# dof_evm.net
KiCad netlist of a schematic drawn in Altium Designer
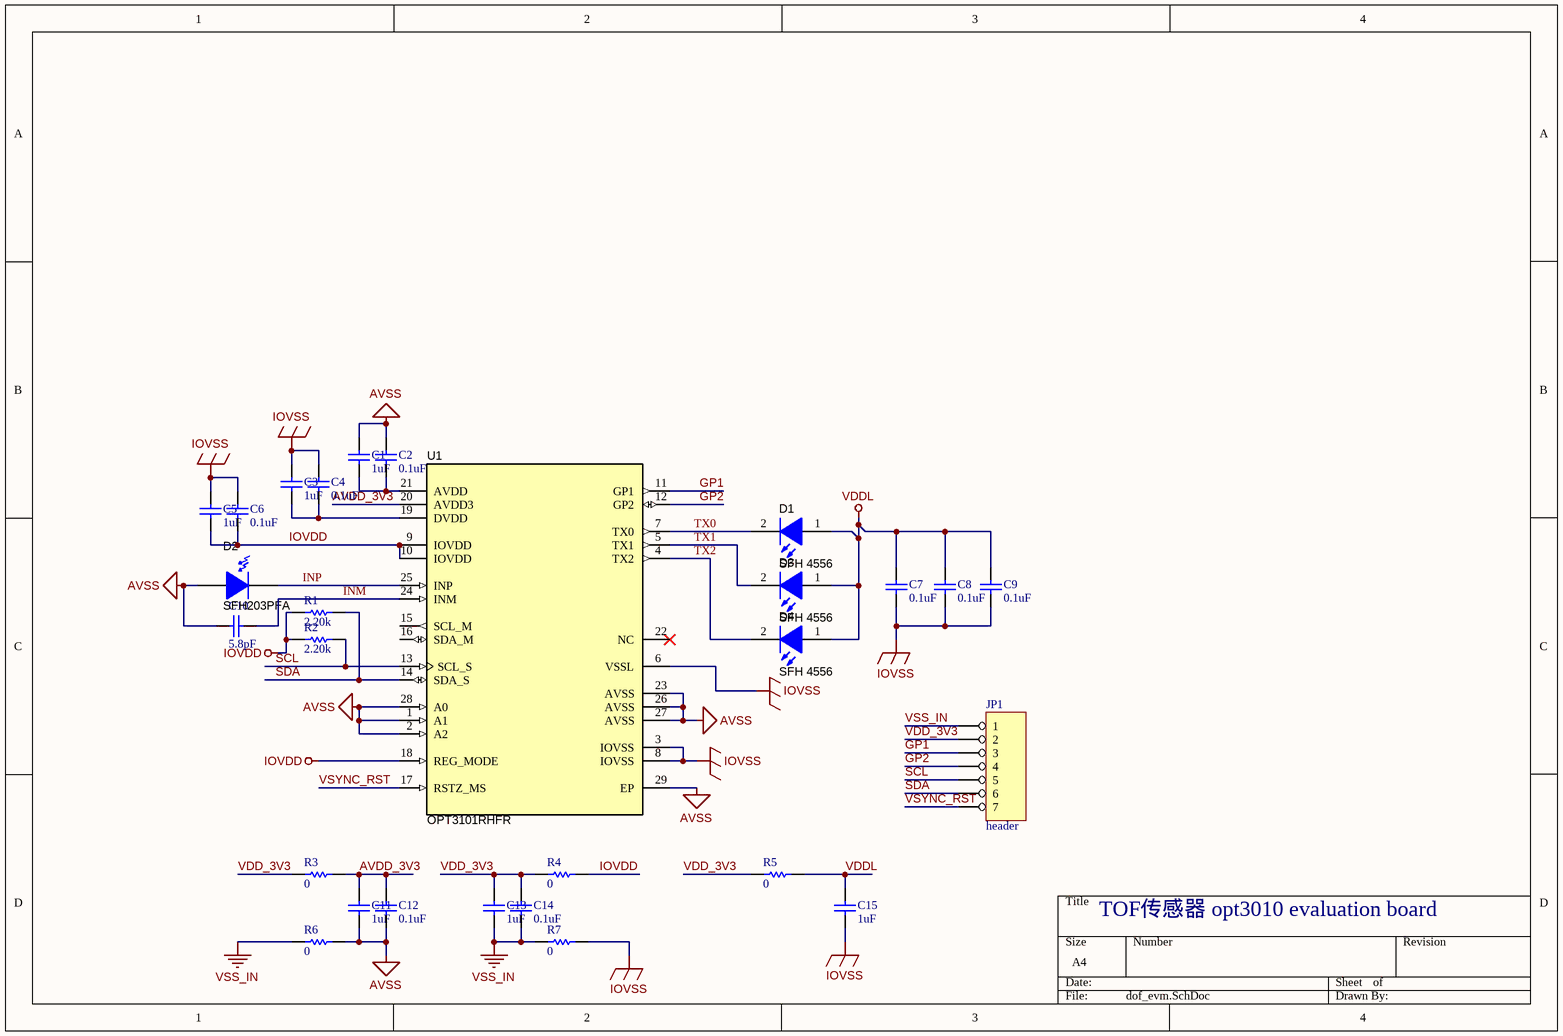
[diagram p0: dof_evm.SchDoc]

(export (version "E")
  (design (tool "Eeschema 10.0.6"))
  (components
    (comp (ref "C1")
      (value "1uF")
      (footprint "0603_C")
      (description "Capacitor")
      (fields (field (name "PUBLISHER") "Altium Limited"))
      (libsource (lib "My Footprint") (part "CAP"))
    )
    (comp (ref "C2")
      (value "0.1uF")
      (footprint "0603_C")
      (description "Capacitor")
      (fields (field (name "PUBLISHER") "Altium Limited"))
      (libsource (lib "My Footprint") (part "CAP"))
    )
    (comp (ref "C3")
      (value "1uF")
      (footprint "0603_C")
      (description "Capacitor")
      (fields (field (name "PUBLISHER") "Altium Limited"))
      (libsource (lib "My Footprint") (part "CAP"))
    )
    (comp (ref "C4")
      (value "0.1uF")
      (footprint "0603_C")
      (description "Capacitor")
      (fields (field (name "PUBLISHER") "Altium Limited"))
      (libsource (lib "My Footprint") (part "CAP"))
    )
    (comp (ref "C5")
      (value "1uF")
      (footprint "0603_C")
      (description "Capacitor")
      (fields (field (name "PUBLISHER") "Altium Limited"))
      (libsource (lib "My Footprint") (part "CAP"))
    )
    (comp (ref "C6")
      (value "0.1uF")
      (footprint "0603_C")
      (description "Capacitor")
      (fields (field (name "PUBLISHER") "Altium Limited"))
      (libsource (lib "My Footprint") (part "CAP"))
    )
    (comp (ref "C7")
      (value "0.1uF")
      (footprint "0603_C")
      (description "Capacitor")
      (fields (field (name "PUBLISHER") "Altium Limited"))
      (libsource (lib "My Footprint") (part "CAP"))
    )
    (comp (ref "C8")
      (value "0.1uF")
      (footprint "0603_C")
      (description "Capacitor")
      (fields (field (name "PUBLISHER") "Altium Limited"))
      (libsource (lib "My Footprint") (part "CAP"))
    )
    (comp (ref "C9")
      (value "0.1uF")
      (footprint "0603_C")
      (description "Capacitor")
      (fields (field (name "PUBLISHER") "Altium Limited"))
      (libsource (lib "My Footprint") (part "CAP"))
    )
    (comp (ref "C10")
      (value "5.8pF")
      (footprint "0603_C")
      (description "Capacitor")
      (fields (field (name "PUBLISHER") "Altium Limited"))
      (libsource (lib "My Footprint") (part "CAP"))
    )
    (comp (ref "C11")
      (value "1uF")
      (footprint "0603_C")
      (description "Capacitor")
      (fields (field (name "PUBLISHER") "Altium Limited"))
      (libsource (lib "My Footprint") (part "CAP"))
    )
    (comp (ref "C12")
      (value "0.1uF")
      (footprint "0603_C")
      (description "Capacitor")
      (fields (field (name "PUBLISHER") "Altium Limited"))
      (libsource (lib "My Footprint") (part "CAP"))
    )
    (comp (ref "C13")
      (value "1uF")
      (footprint "0603_C")
      (description "Capacitor")
      (fields (field (name "PUBLISHER") "Altium Limited"))
      (libsource (lib "My Footprint") (part "CAP"))
    )
    (comp (ref "C14")
      (value "0.1uF")
      (footprint "0603_C")
      (description "Capacitor")
      (fields (field (name "PUBLISHER") "Altium Limited"))
      (libsource (lib "My Footprint") (part "CAP"))
    )
    (comp (ref "C15")
      (value "1uF")
      (footprint "0603_C")
      (description "Capacitor")
      (fields (field (name "PUBLISHER") "Altium Limited"))
      (libsource (lib "My Footprint") (part "CAP"))
    )
    (comp (ref "D1")
      (value "SFH 4556")
      (footprint "SFH4556")
      (description "LED, Infrared, TH")
      (fields (field (name "MANUFACTURER") "OSRAM") (field (name "PUBLISHER") "Texas Instruments"))
      (libsource (lib "My Footprint") (part "SFH 4556"))
    )
    (comp (ref "D2")
      (value "SFH203PFA")
      (footprint "SFH_213")
      (description "Silicon PIN Photodiode, TH")
      (fields (field (name "MANUFACTURER") "OSRAM"))
      (libsource (lib "My Footprint") (part "SFH203PFA"))
    )
    (comp (ref "D3")
      (value "SFH 4556")
      (footprint "SFH4556")
      (description "LED, Infrared, TH")
      (fields (field (name "MANUFACTURER") "OSRAM") (field (name "PUBLISHER") "Texas Instruments"))
      (libsource (lib "My Footprint") (part "SFH 4556"))
    )
    (comp (ref "D4")
      (value "SFH 4556")
      (footprint "SFH4556")
      (description "LED, Infrared, TH")
      (fields (field (name "MANUFACTURER") "OSRAM") (field (name "PUBLISHER") "Texas Instruments"))
      (libsource (lib "My Footprint") (part "SFH 4556"))
    )
    (comp (ref "JP1")
      (value "header")
      (footprint "header7")
      (libsource (lib "My Footprint") (part "HEADER 7"))
    )
    (comp (ref "R1")
      (value "2.20k")
      (footprint "0603_R")
      (description "Resistor")
      (fields (field (name "PUBLISHER") "Altium Limited"))
      (libsource (lib "My Footprint") (part "RES"))
    )
    (comp (ref "R2")
      (value "2.20k")
      (footprint "0603_R")
      (description "Resistor")
      (fields (field (name "PUBLISHER") "Altium Limited"))
      (libsource (lib "My Footprint") (part "RES"))
    )
    (comp (ref "R3")
      (value "0")
      (footprint "0603_R")
      (description "Resistor")
      (fields (field (name "PUBLISHER") "Altium Limited"))
      (libsource (lib "My Footprint") (part "RES"))
    )
    (comp (ref "R4")
      (value "0")
      (footprint "0603_R")
      (description "Resistor")
      (fields (field (name "PUBLISHER") "Altium Limited"))
      (libsource (lib "My Footprint") (part "RES"))
    )
    (comp (ref "R5")
      (value "0")
      (footprint "0603_R")
      (description "Resistor")
      (fields (field (name "PUBLISHER") "Altium Limited"))
      (libsource (lib "My Footprint") (part "RES"))
    )
    (comp (ref "R6")
      (value "0")
      (footprint "0603_R")
      (description "Resistor")
      (fields (field (name "PUBLISHER") "Altium Limited"))
      (libsource (lib "My Footprint") (part "RES"))
    )
    (comp (ref "R7")
      (value "0")
      (footprint "0603_R")
      (description "Resistor")
      (fields (field (name "PUBLISHER") "Altium Limited"))
      (libsource (lib "My Footprint") (part "RES"))
    )
    (comp (ref "U1")
      (value "OPT3101RHFR")
      (footprint "VQFN-28")
      (description "Long Range Proximity/Depth Sensor, RHF0028A (VQFN-28)")
      (fields
        (field (name "ALTERNATE PARTNUMBER") "OPT3101RHFT")
        (field (name "MANUFACTURER") "Texas Instruments")
        (field (name "PUBLISHER") "Texas Instruments")
      )
      (libsource (lib "My Footprint") (part "OPT3101RHFR"))
    )
  )
  (nets
    (net (code "1") (name "/AVDD_3V3") (class "Default")
      (node (ref "C11") (pin "2") (pinfunction "2_2") (pintype "passive"))
      (node (ref "C12") (pin "2") (pinfunction "2_2") (pintype "passive"))
      (node (ref "R3") (pin "2") (pinfunction "2_2") (pintype "passive"))
      (node (ref "U1") (pin "20") (pinfunction "AVDD3_20") (pintype "power_in"))
    )
    (net (code "2") (name "/GP1") (class "Default")
      (node (ref "JP1") (pin "3") (pinfunction "3_3") (pintype "passive"))
      (node (ref "U1") (pin "11") (pinfunction "GP1_11") (pintype "output"))
    )
    (net (code "3") (name "/GP2") (class "Default")
      (node (ref "JP1") (pin "4") (pinfunction "4_4") (pintype "passive"))
      (node (ref "U1") (pin "12") (pinfunction "GP2_12") (pintype "bidirectional"))
    )
    (net (code "4") (name "/INM") (class "Default")
      (node (ref "C10") (pin "1") (pinfunction "1_1") (pintype "passive"))
      (node (ref "U1") (pin "24") (pinfunction "INM_24") (pintype "input"))
    )
    (net (code "5") (name "/INP") (class "Default")
      (node (ref "D2") (pin "2") (pinfunction "C_2") (pintype "passive"))
      (node (ref "U1") (pin "25") (pinfunction "INP_25") (pintype "input"))
    )
    (net (code "6") (name "/SCL") (class "Default")
      (node (ref "JP1") (pin "5") (pinfunction "5_5") (pintype "passive"))
      (node (ref "R2") (pin "2") (pinfunction "2_2") (pintype "passive"))
      (node (ref "U1") (pin "13") (pinfunction "SCL_S_13") (pintype "input"))
    )
    (net (code "7") (name "/SDA") (class "Default")
      (node (ref "JP1") (pin "6") (pinfunction "6_6") (pintype "passive"))
      (node (ref "R1") (pin "2") (pinfunction "2_2") (pintype "passive"))
      (node (ref "U1") (pin "14") (pinfunction "SDA_S_14") (pintype "bidirectional"))
    )
    (net (code "8") (name "/TX0") (class "Default")
      (node (ref "D1") (pin "2") (pinfunction "K_2") (pintype "passive"))
      (node (ref "U1") (pin "7") (pinfunction "TX0_7") (pintype "output"))
    )
    (net (code "9") (name "/TX1") (class "Default")
      (node (ref "D3") (pin "2") (pinfunction "K_2") (pintype "passive"))
      (node (ref "U1") (pin "5") (pinfunction "TX1_5") (pintype "output"))
    )
    (net (code "10") (name "/TX2") (class "Default")
      (node (ref "D4") (pin "2") (pinfunction "K_2") (pintype "passive"))
      (node (ref "U1") (pin "4") (pinfunction "TX2_4") (pintype "output"))
    )
    (net (code "11") (name "/VDD_3V3") (class "Default")
      (node (ref "C13") (pin "2") (pinfunction "2_2") (pintype "passive"))
      (node (ref "C14") (pin "2") (pinfunction "2_2") (pintype "passive"))
      (node (ref "JP1") (pin "2") (pinfunction "2_2") (pintype "passive"))
      (node (ref "R3") (pin "1") (pinfunction "1_1") (pintype "passive"))
      (node (ref "R4") (pin "1") (pinfunction "1_1") (pintype "passive"))
      (node (ref "R5") (pin "1") (pinfunction "1_1") (pintype "passive"))
    )
    (net (code "12") (name "/VSYNC_RST") (class "Default")
      (node (ref "JP1") (pin "7") (pinfunction "7_7") (pintype "passive"))
      (node (ref "U1") (pin "17") (pinfunction "RSTZ_MS_17") (pintype "input"))
    )
    (net (code "13") (name "AVSS") (class "Default")
      (node (ref "C1") (pin "2") (pinfunction "2_2") (pintype "passive"))
      (node (ref "C10") (pin "2") (pinfunction "2_2") (pintype "passive"))
      (node (ref "C11") (pin "1") (pinfunction "1_1") (pintype "passive"))
      (node (ref "C12") (pin "1") (pinfunction "1_1") (pintype "passive"))
      (node (ref "C2") (pin "2") (pinfunction "2_2") (pintype "passive"))
      (node (ref "D2") (pin "1") (pinfunction "A_1") (pintype "passive"))
      (node (ref "R6") (pin "2") (pinfunction "2_2") (pintype "passive"))
      (node (ref "U1") (pin "1") (pinfunction "A1_1") (pintype "input"))
      (node (ref "U1") (pin "2") (pinfunction "A2_2") (pintype "input"))
      (node (ref "U1") (pin "23") (pinfunction "AVSS_23") (pintype "power_in"))
      (node (ref "U1") (pin "26") (pinfunction "AVSS_26") (pintype "power_in"))
      (node (ref "U1") (pin "27") (pinfunction "AVSS_27") (pintype "power_in"))
      (node (ref "U1") (pin "28") (pinfunction "A0_28") (pintype "input"))
      (node (ref "U1") (pin "29") (pinfunction "EP_29") (pintype "passive"))
    )
    (net (code "14") (name "IOVDD") (class "Default")
      (node (ref "C5") (pin "1") (pinfunction "1_1") (pintype "passive"))
      (node (ref "C6") (pin "1") (pinfunction "1_1") (pintype "passive"))
      (node (ref "R1") (pin "1") (pinfunction "1_1") (pintype "passive"))
      (node (ref "R2") (pin "1") (pinfunction "1_1") (pintype "passive"))
      (node (ref "R4") (pin "2") (pinfunction "2_2") (pintype "passive"))
      (node (ref "U1") (pin "10") (pinfunction "IOVDD_10") (pintype "power_in"))
      (node (ref "U1") (pin "18") (pinfunction "REG_MODE_18") (pintype "input"))
      (node (ref "U1") (pin "9") (pinfunction "IOVDD_9") (pintype "power_in"))
    )
    (net (code "15") (name "IOVSS") (class "Default")
      (node (ref "C15") (pin "1") (pinfunction "1_1") (pintype "passive"))
      (node (ref "C3") (pin "2") (pinfunction "2_2") (pintype "passive"))
      (node (ref "C4") (pin "2") (pinfunction "2_2") (pintype "passive"))
      (node (ref "C5") (pin "2") (pinfunction "2_2") (pintype "passive"))
      (node (ref "C6") (pin "2") (pinfunction "2_2") (pintype "passive"))
      (node (ref "C7") (pin "1") (pinfunction "1_1") (pintype "passive"))
      (node (ref "C8") (pin "1") (pinfunction "1_1") (pintype "passive"))
      (node (ref "C9") (pin "1") (pinfunction "1_1") (pintype "passive"))
      (node (ref "R7") (pin "2") (pinfunction "2_2") (pintype "passive"))
      (node (ref "U1") (pin "3") (pinfunction "IOVSS_3") (pintype "power_in"))
      (node (ref "U1") (pin "6") (pinfunction "VSSL_6") (pintype "power_in"))
      (node (ref "U1") (pin "8") (pinfunction "IOVSS_8") (pintype "power_in"))
    )
    (net (code "16") (name "Net-(U1-AVDD)") (class "Default")
      (node (ref "C1") (pin "1") (pinfunction "1_1") (pintype "passive"))
      (node (ref "C2") (pin "1") (pinfunction "1_1") (pintype "passive"))
      (node (ref "U1") (pin "21") (pinfunction "AVDD_21") (pintype "power_in"))
    )
    (net (code "17") (name "Net-(U1-DVDD)") (class "Default")
      (node (ref "C3") (pin "1") (pinfunction "1_1") (pintype "passive"))
      (node (ref "C4") (pin "1") (pinfunction "1_1") (pintype "passive"))
      (node (ref "U1") (pin "19") (pinfunction "DVDD_19") (pintype "power_in"))
    )
    (net (code "18") (name "VDDL") (class "Default")
      (node (ref "C15") (pin "2") (pinfunction "2_2") (pintype "passive"))
      (node (ref "C7") (pin "2") (pinfunction "2_2") (pintype "passive"))
      (node (ref "C8") (pin "2") (pinfunction "2_2") (pintype "passive"))
      (node (ref "C9") (pin "2") (pinfunction "2_2") (pintype "passive"))
      (node (ref "D1") (pin "1") (pinfunction "A_1") (pintype "passive"))
      (node (ref "D3") (pin "1") (pinfunction "A_1") (pintype "passive"))
      (node (ref "D4") (pin "1") (pinfunction "A_1") (pintype "passive"))
      (node (ref "R5") (pin "2") (pinfunction "2_2") (pintype "passive"))
    )
    (net (code "19") (name "VSS_IN") (class "Default")
      (node (ref "C13") (pin "1") (pinfunction "1_1") (pintype "passive"))
      (node (ref "C14") (pin "1") (pinfunction "1_1") (pintype "passive"))
      (node (ref "JP1") (pin "1") (pinfunction "1_1") (pintype "passive"))
      (node (ref "R6") (pin "1") (pinfunction "1_1") (pintype "passive"))
      (node (ref "R7") (pin "1") (pinfunction "1_1") (pintype "passive"))
    )
    (net (code "20") (name "unconnected-(U1-NC-Pad22)") (class "Default")
      (node (ref "U1") (pin "22") (pinfunction "NC_22") (pintype "passive+no_connect"))
    )
    (net (code "21") (name "unconnected-(U1-SCL_M-Pad15)") (class "Default")
      (node (ref "U1") (pin "15") (pinfunction "SCL_M_15") (pintype "output"))
    )
    (net (code "22") (name "unconnected-(U1-SDA_M-Pad16)") (class "Default")
      (node (ref "U1") (pin "16") (pinfunction "SDA_M_16") (pintype "bidirectional"))
    )
  )
)
